# Schematics.net
KiCad netlist of a schematic drawn in Altium Designer
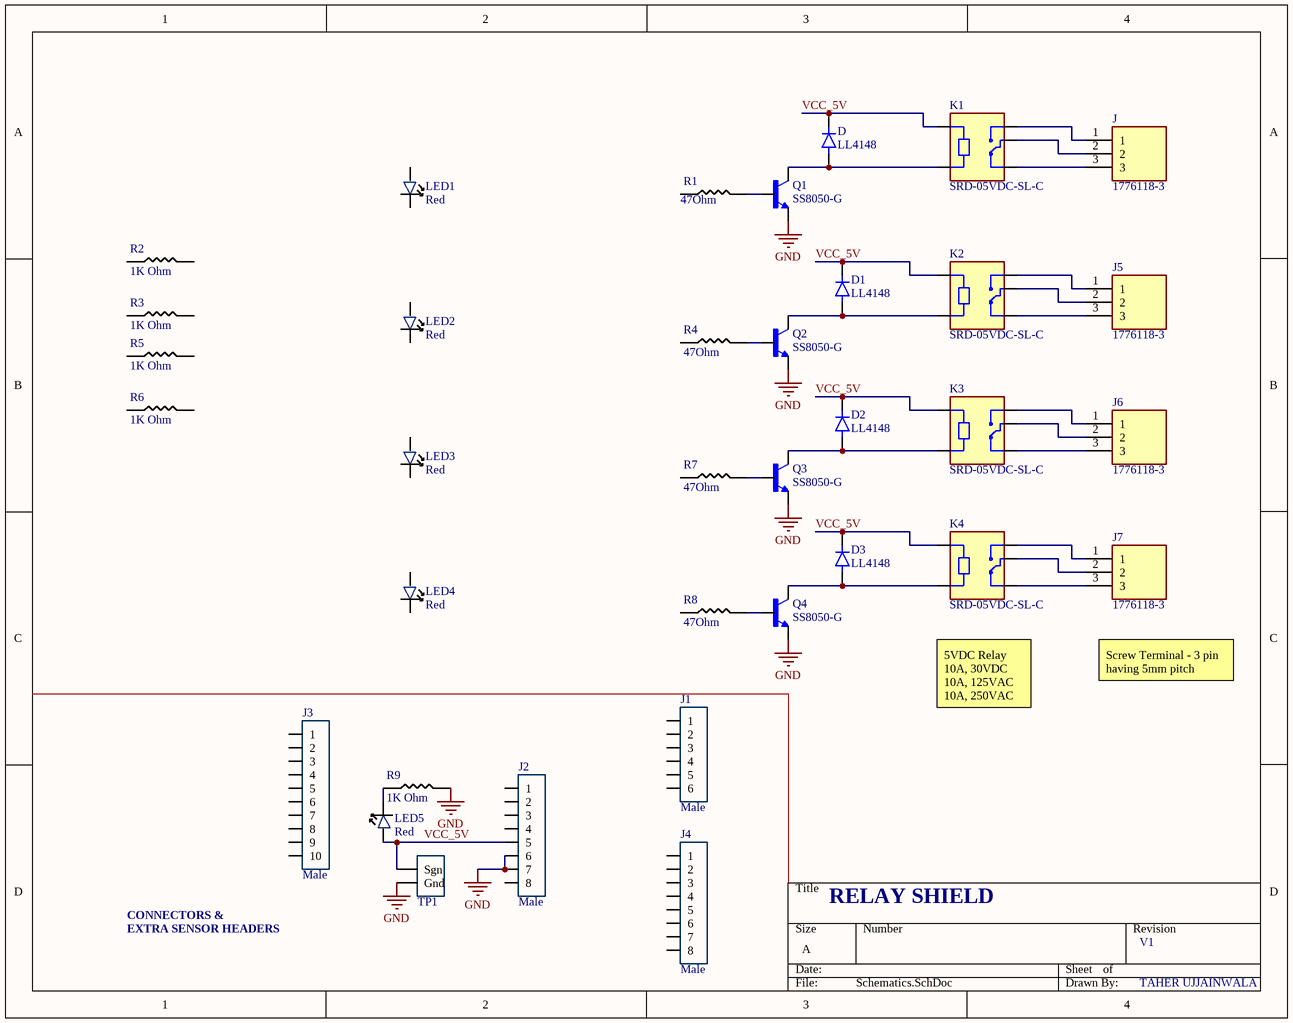
[diagram p0: Schematics.SchDoc]

(export (version "E")
  (design (tool "Eeschema 10.0.6"))
  (components
    (comp (ref "D")
      (value "LL4148")
      (footprint "DIO_LL4148")
      (description "Diode Standard 100V 200mA Surface Mount SOD-80")
      (fields (field (name "MF") "ON Semiconductor"))
      (libsource (lib "LL4148") (part "LL4148"))
    )
    (comp (ref "D1")
      (value "LL4148")
      (footprint "DIO_LL4148")
      (description "Diode Standard 100V 200mA Surface Mount SOD-80")
      (fields (field (name "MF") "ON Semiconductor"))
      (libsource (lib "LL4148") (part "LL4148"))
    )
    (comp (ref "D2")
      (value "LL4148")
      (footprint "DIO_LL4148")
      (description "Diode Standard 100V 200mA Surface Mount SOD-80")
      (fields (field (name "MF") "ON Semiconductor"))
      (libsource (lib "LL4148") (part "LL4148"))
    )
    (comp (ref "D3")
      (value "LL4148")
      (footprint "DIO_LL4148")
      (description "Diode Standard 100V 200mA Surface Mount SOD-80")
      (fields (field (name "MF") "ON Semiconductor"))
      (libsource (lib "LL4148") (part "LL4148"))
    )
    (comp (ref "J")
      (value "1776118-3")
      (footprint "TE_1776118-3")
      (description "Conn Terminal Block F 3 POS 5mm Solder ST Thru-Hole Package")
      (fields (field (name "MF") "TE Connectivity"))
      (libsource (lib "1776118-3") (part "1776118-3"))
    )
    (comp (ref "J1")
      (value "Male")
      (footprint "6_PIN_ARDUINO_100mil")
      (description "6 Position Header Connector 0.100\" (2.54mm) Through Hole Tin")
      (fields (field (name "DIGIKEY PART") "S7004-ND") (field (name "LCSC PART#") "DNP"))
      (libsource (lib "ECEN5730Lib_Manual_2021_08") (part "JM_6_PIN_MALE_ARDUINO"))
    )
    (comp (ref "J2")
      (value "Male")
      (footprint "8_PIN_ARDUINO_100MIL")
      (description "8 Position Header Connector 0.100\" (2.54mm) Through Hole Tin")
      (fields (field (name "DIGIKEY PART") "S7006-ND") (field (name "LCSC PART#") "DNP"))
      (libsource (lib "ECEN5730Lib_Manual_2021_08") (part "JM_8_PIN_MALE_ARDUINO"))
    )
    (comp (ref "J3")
      (value "Male")
      (footprint "10_PIN_ARDUINO_100MIL")
      (description "10 Position Header Connector 0.100\" (2.54mm) Through Hole Tin")
      (fields (field (name "DIGIKEY PART") "S7008-ND") (field (name "LCSC PART#") "DNP"))
      (libsource (lib "ECEN5730Lib_Manual_2021_08") (part "JM_10_PIN_MALE_ARDUINO"))
    )
    (comp (ref "J4")
      (value "Male")
      (footprint "8_PIN_ARDUINO_100MIL")
      (description "8 Position Header Connector 0.100\" (2.54mm) Through Hole Tin")
      (fields (field (name "DIGIKEY PART") "S7006-ND") (field (name "LCSC PART#") "DNP"))
      (libsource (lib "ECEN5730Lib_Manual_2021_08") (part "JM_8_PIN_MALE_ARDUINO"))
    )
    (comp (ref "J5")
      (value "1776118-3")
      (footprint "TE_1776118-3")
      (description "Conn Terminal Block F 3 POS 5mm Solder ST Thru-Hole Package")
      (fields (field (name "MF") "TE Connectivity"))
      (libsource (lib "1776118-3") (part "1776118-3"))
    )
    (comp (ref "J6")
      (value "1776118-3")
      (footprint "TE_1776118-3")
      (description "Conn Terminal Block F 3 POS 5mm Solder ST Thru-Hole Package")
      (fields (field (name "MF") "TE Connectivity"))
      (libsource (lib "1776118-3") (part "1776118-3"))
    )
    (comp (ref "J7")
      (value "1776118-3")
      (footprint "TE_1776118-3")
      (description "Conn Terminal Block F 3 POS 5mm Solder ST Thru-Hole Package")
      (fields (field (name "MF") "TE Connectivity"))
      (libsource (lib "1776118-3") (part "1776118-3"))
    )
    (comp (ref "K1")
      (value "SRD-05VDC-SL-C")
      (footprint "RELAY_SRD-05VDC-SL-C")
      (fields (field (name "MF") "Songle Relay"))
      (libsource (lib "SRD-05VDC-SL-C") (part "SRD-05VDC-SL-C"))
    )
    (comp (ref "K2")
      (value "SRD-05VDC-SL-C")
      (footprint "RELAY_SRD-05VDC-SL-C")
      (fields (field (name "MF") "Songle Relay"))
      (libsource (lib "SRD-05VDC-SL-C") (part "SRD-05VDC-SL-C"))
    )
    (comp (ref "K3")
      (value "SRD-05VDC-SL-C")
      (footprint "RELAY_SRD-05VDC-SL-C")
      (fields (field (name "MF") "Songle Relay"))
      (libsource (lib "SRD-05VDC-SL-C") (part "SRD-05VDC-SL-C"))
    )
    (comp (ref "K4")
      (value "SRD-05VDC-SL-C")
      (footprint "RELAY_SRD-05VDC-SL-C")
      (fields (field (name "MF") "Songle Relay"))
      (libsource (lib "SRD-05VDC-SL-C") (part "SRD-05VDC-SL-C"))
    )
    (comp (ref "LED1")
      (value "Red")
      (footprint "LED_0603")
      (description "LIGHT EMITTING DIODES (LED) RED 520~625NM 90~100MCD@20MA TOP VIEW 0603 ROHS")
      (fields (field (name "MFR PART #") "KT-0603R") (field (name "LCSC PART#") "C2286"))
      (libsource (lib "ECEN5730Lib_JLC_2021_08") (part "LED_RED_0603"))
    )
    (comp (ref "LED2")
      (value "Red")
      (footprint "LED_0603")
      (description "LIGHT EMITTING DIODES (LED) RED 520~625NM 90~100MCD@20MA TOP VIEW 0603 ROHS")
      (fields (field (name "MFR PART #") "KT-0603R") (field (name "LCSC PART#") "C2286"))
      (libsource (lib "ECEN5730Lib_JLC_2021_08") (part "LED_RED_0603"))
    )
    (comp (ref "LED3")
      (value "Red")
      (footprint "LED_0603")
      (description "LIGHT EMITTING DIODES (LED) RED 520~625NM 90~100MCD@20MA TOP VIEW 0603 ROHS")
      (fields (field (name "MFR PART #") "KT-0603R") (field (name "LCSC PART#") "C2286"))
      (libsource (lib "ECEN5730Lib_JLC_2021_08") (part "LED_RED_0603"))
    )
    (comp (ref "LED4")
      (value "Red")
      (footprint "LED_0603")
      (description "LIGHT EMITTING DIODES (LED) RED 520~625NM 90~100MCD@20MA TOP VIEW 0603 ROHS")
      (fields (field (name "MFR PART #") "KT-0603R") (field (name "LCSC PART#") "C2286"))
      (libsource (lib "ECEN5730Lib_JLC_2021_08") (part "LED_RED_0603"))
    )
    (comp (ref "LED5")
      (value "Red")
      (footprint "LED")
      (description "Red 638nm LED Indication - Discrete 1.8V 1206 (3216 Metric)")
      (fields (field (name "DIGIKEY PART") "160-1167-1-ND") (field (name "Comment") "LTST-C150CKT"))
      (libsource (lib "ECEN5730Lib_Manual_2021_08") (part "LED_1206"))
    )
    (comp (ref "Q1")
      (value "SS8050-G")
      (footprint "TRANS_SS8050-G")
      (description "Bipolar (BJT) Transistor NPN 25 V 1.5 A 100MHz 300 mW Surface Mount SOT-23-3")
      (fields (field (name "MF") "Comchip Technology"))
      (libsource (lib "SS8050-G") (part "SS8050-G"))
    )
    (comp (ref "Q2")
      (value "SS8050-G")
      (footprint "TRANS_SS8050-G")
      (description "Bipolar (BJT) Transistor NPN 25 V 1.5 A 100MHz 300 mW Surface Mount SOT-23-3")
      (fields (field (name "MF") "Comchip Technology"))
      (libsource (lib "SS8050-G") (part "SS8050-G"))
    )
    (comp (ref "Q3")
      (value "SS8050-G")
      (footprint "TRANS_SS8050-G")
      (description "Bipolar (BJT) Transistor NPN 25 V 1.5 A 100MHz 300 mW Surface Mount SOT-23-3")
      (fields (field (name "MF") "Comchip Technology"))
      (libsource (lib "SS8050-G") (part "SS8050-G"))
    )
    (comp (ref "Q4")
      (value "SS8050-G")
      (footprint "TRANS_SS8050-G")
      (description "Bipolar (BJT) Transistor NPN 25 V 1.5 A 100MHz 300 mW Surface Mount SOT-23-3")
      (fields (field (name "MF") "Comchip Technology"))
      (libsource (lib "SS8050-G") (part "SS8050-G"))
    )
    (comp (ref "R1")
      (value "47Ohm")
      (footprint "1206_Passive_Resitor")
      (description "47Ω ±5% 0.25W ±200ppm/℃ 1206 Chip Resistor - Surface Mount RoHS")
      (fields (field (name "MFR PART #") "1206W4J0470T5E") (field (name "LCSC PART#") "C25384"))
      (libsource (lib "ECEN5730Lib_JLC_2021_08") (part "R_47Ohm_1206"))
    )
    (comp (ref "R2")
      (value "1K Ohm")
      (footprint "0402_Passive_Resistor")
      (description "1 kOhms chip resistor SURFACE MOUNT 1KOHMS ±1% 1/16W 0402 ROHS")
      (fields (field (name "MFR PART #") "0402WGF1001TCE") (field (name "LCSC PART#") "C11702"))
      (libsource (lib "ECEN5730Lib_JLC_2021_08") (part "R_1K_0402"))
    )
    (comp (ref "R3")
      (value "1K Ohm")
      (footprint "0402_Passive_Resistor")
      (description "1 kOhms chip resistor SURFACE MOUNT 1KOHMS ±1% 1/16W 0402 ROHS")
      (fields (field (name "MFR PART #") "0402WGF1001TCE") (field (name "LCSC PART#") "C11702"))
      (libsource (lib "ECEN5730Lib_JLC_2021_08") (part "R_1K_0402"))
    )
    (comp (ref "R4")
      (value "47Ohm")
      (footprint "1206_Passive_Resitor")
      (description "47Ω ±5% 0.25W ±200ppm/℃ 1206 Chip Resistor - Surface Mount RoHS")
      (fields (field (name "MFR PART #") "1206W4J0470T5E") (field (name "LCSC PART#") "C25384"))
      (libsource (lib "ECEN5730Lib_JLC_2021_08") (part "R_47Ohm_1206"))
    )
    (comp (ref "R5")
      (value "1K Ohm")
      (footprint "0402_Passive_Resistor")
      (description "1 kOhms chip resistor SURFACE MOUNT 1KOHMS ±1% 1/16W 0402 ROHS")
      (fields (field (name "MFR PART #") "0402WGF1001TCE") (field (name "LCSC PART#") "C11702"))
      (libsource (lib "ECEN5730Lib_JLC_2021_08") (part "R_1K_0402"))
    )
    (comp (ref "R6")
      (value "1K Ohm")
      (footprint "0402_Passive_Resistor")
      (description "1 kOhms chip resistor SURFACE MOUNT 1KOHMS ±1% 1/16W 0402 ROHS")
      (fields (field (name "MFR PART #") "0402WGF1001TCE") (field (name "LCSC PART#") "C11702"))
      (libsource (lib "ECEN5730Lib_JLC_2021_08") (part "R_1K_0402"))
    )
    (comp (ref "R7")
      (value "47Ohm")
      (footprint "1206_Passive_Resitor")
      (description "47Ω ±5% 0.25W ±200ppm/℃ 1206 Chip Resistor - Surface Mount RoHS")
      (fields (field (name "MFR PART #") "1206W4J0470T5E") (field (name "LCSC PART#") "C25384"))
      (libsource (lib "ECEN5730Lib_JLC_2021_08") (part "R_47Ohm_1206"))
    )
    (comp (ref "R8")
      (value "47Ohm")
      (footprint "1206_Passive_Resitor")
      (description "47Ω ±5% 0.25W ±200ppm/℃ 1206 Chip Resistor - Surface Mount RoHS")
      (fields (field (name "MFR PART #") "1206W4J0470T5E") (field (name "LCSC PART#") "C25384"))
      (libsource (lib "ECEN5730Lib_JLC_2021_08") (part "R_47Ohm_1206"))
    )
    (comp (ref "R9")
      (value "1K Ohm")
      (footprint "1206_Passive_Resitor")
      (description "1 kOhms ±1% 0.5W, 1/2W Chip Resistor 1206 (3216 Metric) Anti-Sulfur, Moisture Resistant Thin Film")
      (fields
        (field (name "DIGIKEY PART") "RNCP1206FTD1K00CT-ND")
        (field (name "MFR PART #") "1206W4F1001T5")
      )
      (libsource (lib "ECEN5730Lib_Manual_2021_08") (part "R_1K_1206"))
    )
    (comp (ref "TP1")
      (value "10x Probe TP")
      (footprint "TP10x_Probe")
      (description "Test Point 300 mil centers")
      (libsource (lib "ECEN5730Lib_Manual_2021_08") (part "TP_10x_Probe"))
    )
  )
  (nets
    (net (code "1") (name "/VCC_5V") (class "Default")
      (node (ref "D") (pin "C") (pinfunction "C_C") (pintype "passive"))
      (node (ref "D1") (pin "C") (pinfunction "C_C") (pintype "passive"))
      (node (ref "D2") (pin "C") (pinfunction "C_C") (pintype "passive"))
      (node (ref "D3") (pin "C") (pinfunction "C_C") (pintype "passive"))
      (node (ref "J2") (pin "5") (pinfunction "5_5") (pintype "passive"))
      (node (ref "K1") (pin "A1") (pinfunction "A1_A1") (pintype "passive"))
      (node (ref "K2") (pin "A1") (pinfunction "A1_A1") (pintype "passive"))
      (node (ref "K3") (pin "A1") (pinfunction "A1_A1") (pintype "passive"))
      (node (ref "K4") (pin "A1") (pinfunction "A1_A1") (pintype "passive"))
      (node (ref "LED5") (pin "2") (pinfunction "2_2") (pintype "passive"))
      (node (ref "TP1") (pin "1") (pinfunction "Sgn_1") (pintype "passive"))
    )
    (net (code "2") (name "GND") (class "Default")
      (node (ref "J2") (pin "6") (pinfunction "6_6") (pintype "passive"))
      (node (ref "J2") (pin "7") (pinfunction "7_7") (pintype "passive"))
      (node (ref "Q1") (pin "2") (pinfunction "E_2") (pintype "passive"))
      (node (ref "Q2") (pin "2") (pinfunction "E_2") (pintype "passive"))
      (node (ref "Q3") (pin "2") (pinfunction "E_2") (pintype "passive"))
      (node (ref "Q4") (pin "2") (pinfunction "E_2") (pintype "passive"))
      (node (ref "R9") (pin "2") (pinfunction "2_2") (pintype "passive"))
      (node (ref "TP1") (pin "2") (pinfunction "Gnd_2") (pintype "passive"))
    )
    (net (code "3") (name "Net-(J-Pad1)") (class "Default")
      (node (ref "J") (pin "1") (pinfunction "1_1") (pintype "passive"))
      (node (ref "K1") (pin "NO") (pinfunction "NO_NO") (pintype "passive"))
    )
    (net (code "4") (name "Net-(J-Pad2)") (class "Default")
      (node (ref "J") (pin "2") (pinfunction "2_2") (pintype "passive"))
      (node (ref "K1") (pin "COM") (pinfunction "COM_COM") (pintype "passive"))
    )
    (net (code "5") (name "Net-(J-Pad3)") (class "Default")
      (node (ref "J") (pin "3") (pinfunction "3_3") (pintype "passive"))
      (node (ref "K1") (pin "NC") (pinfunction "NC_NC") (pintype "passive"))
    )
    (net (code "6") (name "Net-(J5-Pad1)") (class "Default")
      (node (ref "J5") (pin "1") (pinfunction "1_1") (pintype "passive"))
      (node (ref "K2") (pin "NO") (pinfunction "NO_NO") (pintype "passive"))
    )
    (net (code "7") (name "Net-(J5-Pad2)") (class "Default")
      (node (ref "J5") (pin "2") (pinfunction "2_2") (pintype "passive"))
      (node (ref "K2") (pin "COM") (pinfunction "COM_COM") (pintype "passive"))
    )
    (net (code "8") (name "Net-(J5-Pad3)") (class "Default")
      (node (ref "J5") (pin "3") (pinfunction "3_3") (pintype "passive"))
      (node (ref "K2") (pin "NC") (pinfunction "NC_NC") (pintype "passive"))
    )
    (net (code "9") (name "Net-(J6-Pad1)") (class "Default")
      (node (ref "J6") (pin "1") (pinfunction "1_1") (pintype "passive"))
      (node (ref "K3") (pin "NO") (pinfunction "NO_NO") (pintype "passive"))
    )
    (net (code "10") (name "Net-(J6-Pad2)") (class "Default")
      (node (ref "J6") (pin "2") (pinfunction "2_2") (pintype "passive"))
      (node (ref "K3") (pin "COM") (pinfunction "COM_COM") (pintype "passive"))
    )
    (net (code "11") (name "Net-(J6-Pad3)") (class "Default")
      (node (ref "J6") (pin "3") (pinfunction "3_3") (pintype "passive"))
      (node (ref "K3") (pin "NC") (pinfunction "NC_NC") (pintype "passive"))
    )
    (net (code "12") (name "Net-(J7-Pad1)") (class "Default")
      (node (ref "J7") (pin "1") (pinfunction "1_1") (pintype "passive"))
      (node (ref "K4") (pin "NO") (pinfunction "NO_NO") (pintype "passive"))
    )
    (net (code "13") (name "Net-(J7-Pad2)") (class "Default")
      (node (ref "J7") (pin "2") (pinfunction "2_2") (pintype "passive"))
      (node (ref "K4") (pin "COM") (pinfunction "COM_COM") (pintype "passive"))
    )
    (net (code "14") (name "Net-(J7-Pad3)") (class "Default")
      (node (ref "J7") (pin "3") (pinfunction "3_3") (pintype "passive"))
      (node (ref "K4") (pin "NC") (pinfunction "NC_NC") (pintype "passive"))
    )
    (net (code "15") (name "Net-(LED5-Pad1)") (class "Default")
      (node (ref "LED5") (pin "1") (pinfunction "1_1") (pintype "passive"))
      (node (ref "R9") (pin "1") (pinfunction "1_1") (pintype "passive"))
    )
    (net (code "16") (name "Net-(Q1-B)") (class "Default")
      (node (ref "Q1") (pin "1") (pinfunction "B_1") (pintype "passive"))
      (node (ref "R1") (pin "2") (pinfunction "2_2") (pintype "passive"))
    )
    (net (code "17") (name "Net-(Q1-C)") (class "Default")
      (node (ref "D") (pin "A") (pinfunction "A_A") (pintype "passive"))
      (node (ref "K1") (pin "A2") (pinfunction "A2_A2") (pintype "passive"))
      (node (ref "Q1") (pin "3") (pinfunction "C_3") (pintype "passive"))
    )
    (net (code "18") (name "Net-(Q2-B)") (class "Default")
      (node (ref "Q2") (pin "1") (pinfunction "B_1") (pintype "passive"))
      (node (ref "R4") (pin "2") (pinfunction "2_2") (pintype "passive"))
    )
    (net (code "19") (name "Net-(Q2-C)") (class "Default")
      (node (ref "D1") (pin "A") (pinfunction "A_A") (pintype "passive"))
      (node (ref "K2") (pin "A2") (pinfunction "A2_A2") (pintype "passive"))
      (node (ref "Q2") (pin "3") (pinfunction "C_3") (pintype "passive"))
    )
    (net (code "20") (name "Net-(Q3-B)") (class "Default")
      (node (ref "Q3") (pin "1") (pinfunction "B_1") (pintype "passive"))
      (node (ref "R7") (pin "2") (pinfunction "2_2") (pintype "passive"))
    )
    (net (code "21") (name "Net-(Q3-C)") (class "Default")
      (node (ref "D2") (pin "A") (pinfunction "A_A") (pintype "passive"))
      (node (ref "K3") (pin "A2") (pinfunction "A2_A2") (pintype "passive"))
      (node (ref "Q3") (pin "3") (pinfunction "C_3") (pintype "passive"))
    )
    (net (code "22") (name "Net-(Q4-B)") (class "Default")
      (node (ref "Q4") (pin "1") (pinfunction "B_1") (pintype "passive"))
      (node (ref "R8") (pin "2") (pinfunction "2_2") (pintype "passive"))
    )
    (net (code "23") (name "Net-(Q4-C)") (class "Default")
      (node (ref "D3") (pin "A") (pinfunction "A_A") (pintype "passive"))
      (node (ref "K4") (pin "A2") (pinfunction "A2_A2") (pintype "passive"))
      (node (ref "Q4") (pin "3") (pinfunction "C_3") (pintype "passive"))
    )
    (net (code "24") (name "unconnected-(J1-Pad1)") (class "Default")
      (node (ref "J1") (pin "1") (pinfunction "1_1") (pintype "passive"))
    )
    (net (code "25") (name "unconnected-(J1-Pad2)") (class "Default")
      (node (ref "J1") (pin "2") (pinfunction "2_2") (pintype "passive"))
    )
    (net (code "26") (name "unconnected-(J1-Pad3)") (class "Default")
      (node (ref "J1") (pin "3") (pinfunction "3_3") (pintype "passive"))
    )
    (net (code "27") (name "unconnected-(J1-Pad4)") (class "Default")
      (node (ref "J1") (pin "4") (pinfunction "4_4") (pintype "passive"))
    )
    (net (code "28") (name "unconnected-(J1-Pad5)") (class "Default")
      (node (ref "J1") (pin "5") (pinfunction "5_5") (pintype "passive"))
    )
    (net (code "29") (name "unconnected-(J1-Pad6)") (class "Default")
      (node (ref "J1") (pin "6") (pinfunction "6_6") (pintype "passive"))
    )
    (net (code "30") (name "unconnected-(J2-Pad1)") (class "Default")
      (node (ref "J2") (pin "1") (pinfunction "1_1") (pintype "passive"))
    )
    (net (code "31") (name "unconnected-(J2-Pad2)") (class "Default")
      (node (ref "J2") (pin "2") (pinfunction "2_2") (pintype "passive"))
    )
    (net (code "32") (name "unconnected-(J2-Pad3)") (class "Default")
      (node (ref "J2") (pin "3") (pinfunction "3_3") (pintype "passive"))
    )
    (net (code "33") (name "unconnected-(J2-Pad4)") (class "Default")
      (node (ref "J2") (pin "4") (pinfunction "4_4") (pintype "passive"))
    )
    (net (code "34") (name "unconnected-(J2-Pad8)") (class "Default")
      (node (ref "J2") (pin "8") (pinfunction "8_8") (pintype "passive"))
    )
    (net (code "35") (name "unconnected-(J3-Pad1)") (class "Default")
      (node (ref "J3") (pin "1") (pinfunction "1_1") (pintype "passive"))
    )
    (net (code "36") (name "unconnected-(J3-Pad2)") (class "Default")
      (node (ref "J3") (pin "2") (pinfunction "2_2") (pintype "passive"))
    )
    (net (code "37") (name "unconnected-(J3-Pad3)") (class "Default")
      (node (ref "J3") (pin "3") (pinfunction "3_3") (pintype "passive"))
    )
    (net (code "38") (name "unconnected-(J3-Pad4)") (class "Default")
      (node (ref "J3") (pin "4") (pinfunction "4_4") (pintype "passive"))
    )
    (net (code "39") (name "unconnected-(J3-Pad5)") (class "Default")
      (node (ref "J3") (pin "5") (pinfunction "5_5") (pintype "passive"))
    )
    (net (code "40") (name "unconnected-(J3-Pad6)") (class "Default")
      (node (ref "J3") (pin "6") (pinfunction "6_6") (pintype "passive"))
    )
    (net (code "41") (name "unconnected-(J3-Pad7)") (class "Default")
      (node (ref "J3") (pin "7") (pinfunction "7_7") (pintype "passive"))
    )
    (net (code "42") (name "unconnected-(J3-Pad8)") (class "Default")
      (node (ref "J3") (pin "8") (pinfunction "8_8") (pintype "passive"))
    )
    (net (code "43") (name "unconnected-(J3-Pad9)") (class "Default")
      (node (ref "J3") (pin "9") (pinfunction "9_9") (pintype "passive"))
    )
    (net (code "44") (name "unconnected-(J3-Pad10)") (class "Default")
      (node (ref "J3") (pin "10") (pinfunction "10_10") (pintype "passive"))
    )
    (net (code "45") (name "unconnected-(J4-Pad1)") (class "Default")
      (node (ref "J4") (pin "1") (pinfunction "1_1") (pintype "passive"))
    )
    (net (code "46") (name "unconnected-(J4-Pad2)") (class "Default")
      (node (ref "J4") (pin "2") (pinfunction "2_2") (pintype "passive"))
    )
    (net (code "47") (name "unconnected-(J4-Pad3)") (class "Default")
      (node (ref "J4") (pin "3") (pinfunction "3_3") (pintype "passive"))
    )
    (net (code "48") (name "unconnected-(J4-Pad4)") (class "Default")
      (node (ref "J4") (pin "4") (pinfunction "4_4") (pintype "passive"))
    )
    (net (code "49") (name "unconnected-(J4-Pad5)") (class "Default")
      (node (ref "J4") (pin "5") (pinfunction "5_5") (pintype "passive"))
    )
    (net (code "50") (name "unconnected-(J4-Pad6)") (class "Default")
      (node (ref "J4") (pin "6") (pinfunction "6_6") (pintype "passive"))
    )
    (net (code "51") (name "unconnected-(J4-Pad7)") (class "Default")
      (node (ref "J4") (pin "7") (pinfunction "7_7") (pintype "passive"))
    )
    (net (code "52") (name "unconnected-(J4-Pad8)") (class "Default")
      (node (ref "J4") (pin "8") (pinfunction "8_8") (pintype "passive"))
    )
    (net (code "53") (name "unconnected-(LED1-Pad1)") (class "Default")
      (node (ref "LED1") (pin "1") (pinfunction "1_1") (pintype "passive"))
    )
    (net (code "54") (name "unconnected-(LED1-Pad2)") (class "Default")
      (node (ref "LED1") (pin "2") (pinfunction "2_2") (pintype "passive"))
    )
    (net (code "55") (name "unconnected-(LED2-Pad1)") (class "Default")
      (node (ref "LED2") (pin "1") (pinfunction "1_1") (pintype "passive"))
    )
    (net (code "56") (name "unconnected-(LED2-Pad2)") (class "Default")
      (node (ref "LED2") (pin "2") (pinfunction "2_2") (pintype "passive"))
    )
    (net (code "57") (name "unconnected-(LED3-Pad1)") (class "Default")
      (node (ref "LED3") (pin "1") (pinfunction "1_1") (pintype "passive"))
    )
    (net (code "58") (name "unconnected-(LED3-Pad2)") (class "Default")
      (node (ref "LED3") (pin "2") (pinfunction "2_2") (pintype "passive"))
    )
    (net (code "59") (name "unconnected-(LED4-Pad1)") (class "Default")
      (node (ref "LED4") (pin "1") (pinfunction "1_1") (pintype "passive"))
    )
    (net (code "60") (name "unconnected-(LED4-Pad2)") (class "Default")
      (node (ref "LED4") (pin "2") (pinfunction "2_2") (pintype "passive"))
    )
    (net (code "61") (name "unconnected-(R1-Pad1)") (class "Default")
      (node (ref "R1") (pin "1") (pinfunction "1_1") (pintype "passive"))
    )
    (net (code "62") (name "unconnected-(R2-Pad1)") (class "Default")
      (node (ref "R2") (pin "1") (pinfunction "1_1") (pintype "passive"))
    )
    (net (code "63") (name "unconnected-(R2-Pad2)") (class "Default")
      (node (ref "R2") (pin "2") (pinfunction "2_2") (pintype "passive"))
    )
    (net (code "64") (name "unconnected-(R3-Pad1)") (class "Default")
      (node (ref "R3") (pin "1") (pinfunction "1_1") (pintype "passive"))
    )
    (net (code "65") (name "unconnected-(R3-Pad2)") (class "Default")
      (node (ref "R3") (pin "2") (pinfunction "2_2") (pintype "passive"))
    )
    (net (code "66") (name "unconnected-(R4-Pad1)") (class "Default")
      (node (ref "R4") (pin "1") (pinfunction "1_1") (pintype "passive"))
    )
    (net (code "67") (name "unconnected-(R5-Pad1)") (class "Default")
      (node (ref "R5") (pin "1") (pinfunction "1_1") (pintype "passive"))
    )
    (net (code "68") (name "unconnected-(R5-Pad2)") (class "Default")
      (node (ref "R5") (pin "2") (pinfunction "2_2") (pintype "passive"))
    )
    (net (code "69") (name "unconnected-(R6-Pad1)") (class "Default")
      (node (ref "R6") (pin "1") (pinfunction "1_1") (pintype "passive"))
    )
    (net (code "70") (name "unconnected-(R6-Pad2)") (class "Default")
      (node (ref "R6") (pin "2") (pinfunction "2_2") (pintype "passive"))
    )
    (net (code "71") (name "unconnected-(R7-Pad1)") (class "Default")
      (node (ref "R7") (pin "1") (pinfunction "1_1") (pintype "passive"))
    )
    (net (code "72") (name "unconnected-(R8-Pad1)") (class "Default")
      (node (ref "R8") (pin "1") (pinfunction "1_1") (pintype "passive"))
    )
  )
)
